# EVAL_51296_V2.net
KiCad netlist of a schematic drawn in EAGLE
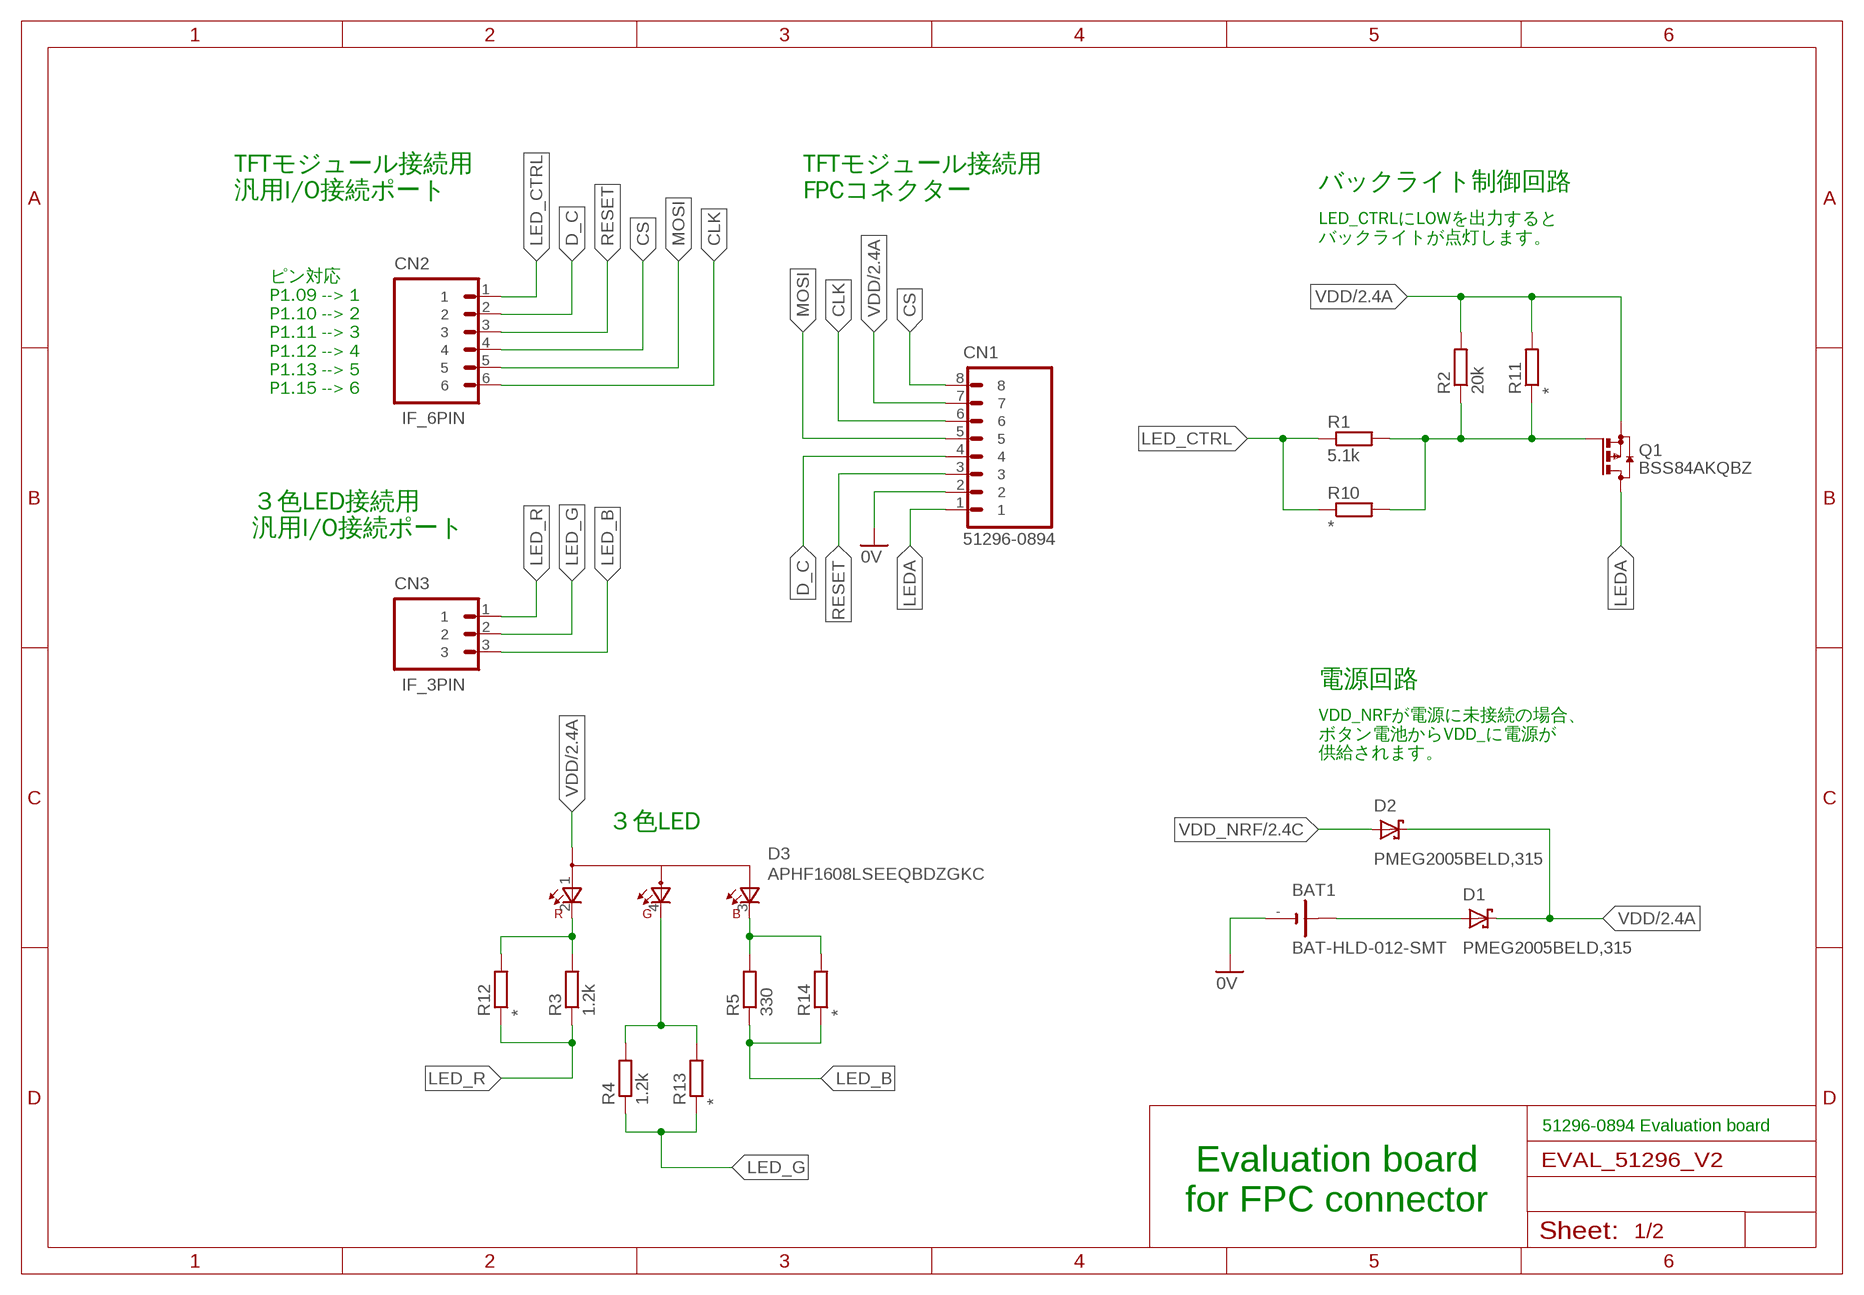
[diagram p0: schematic, sheet 1]
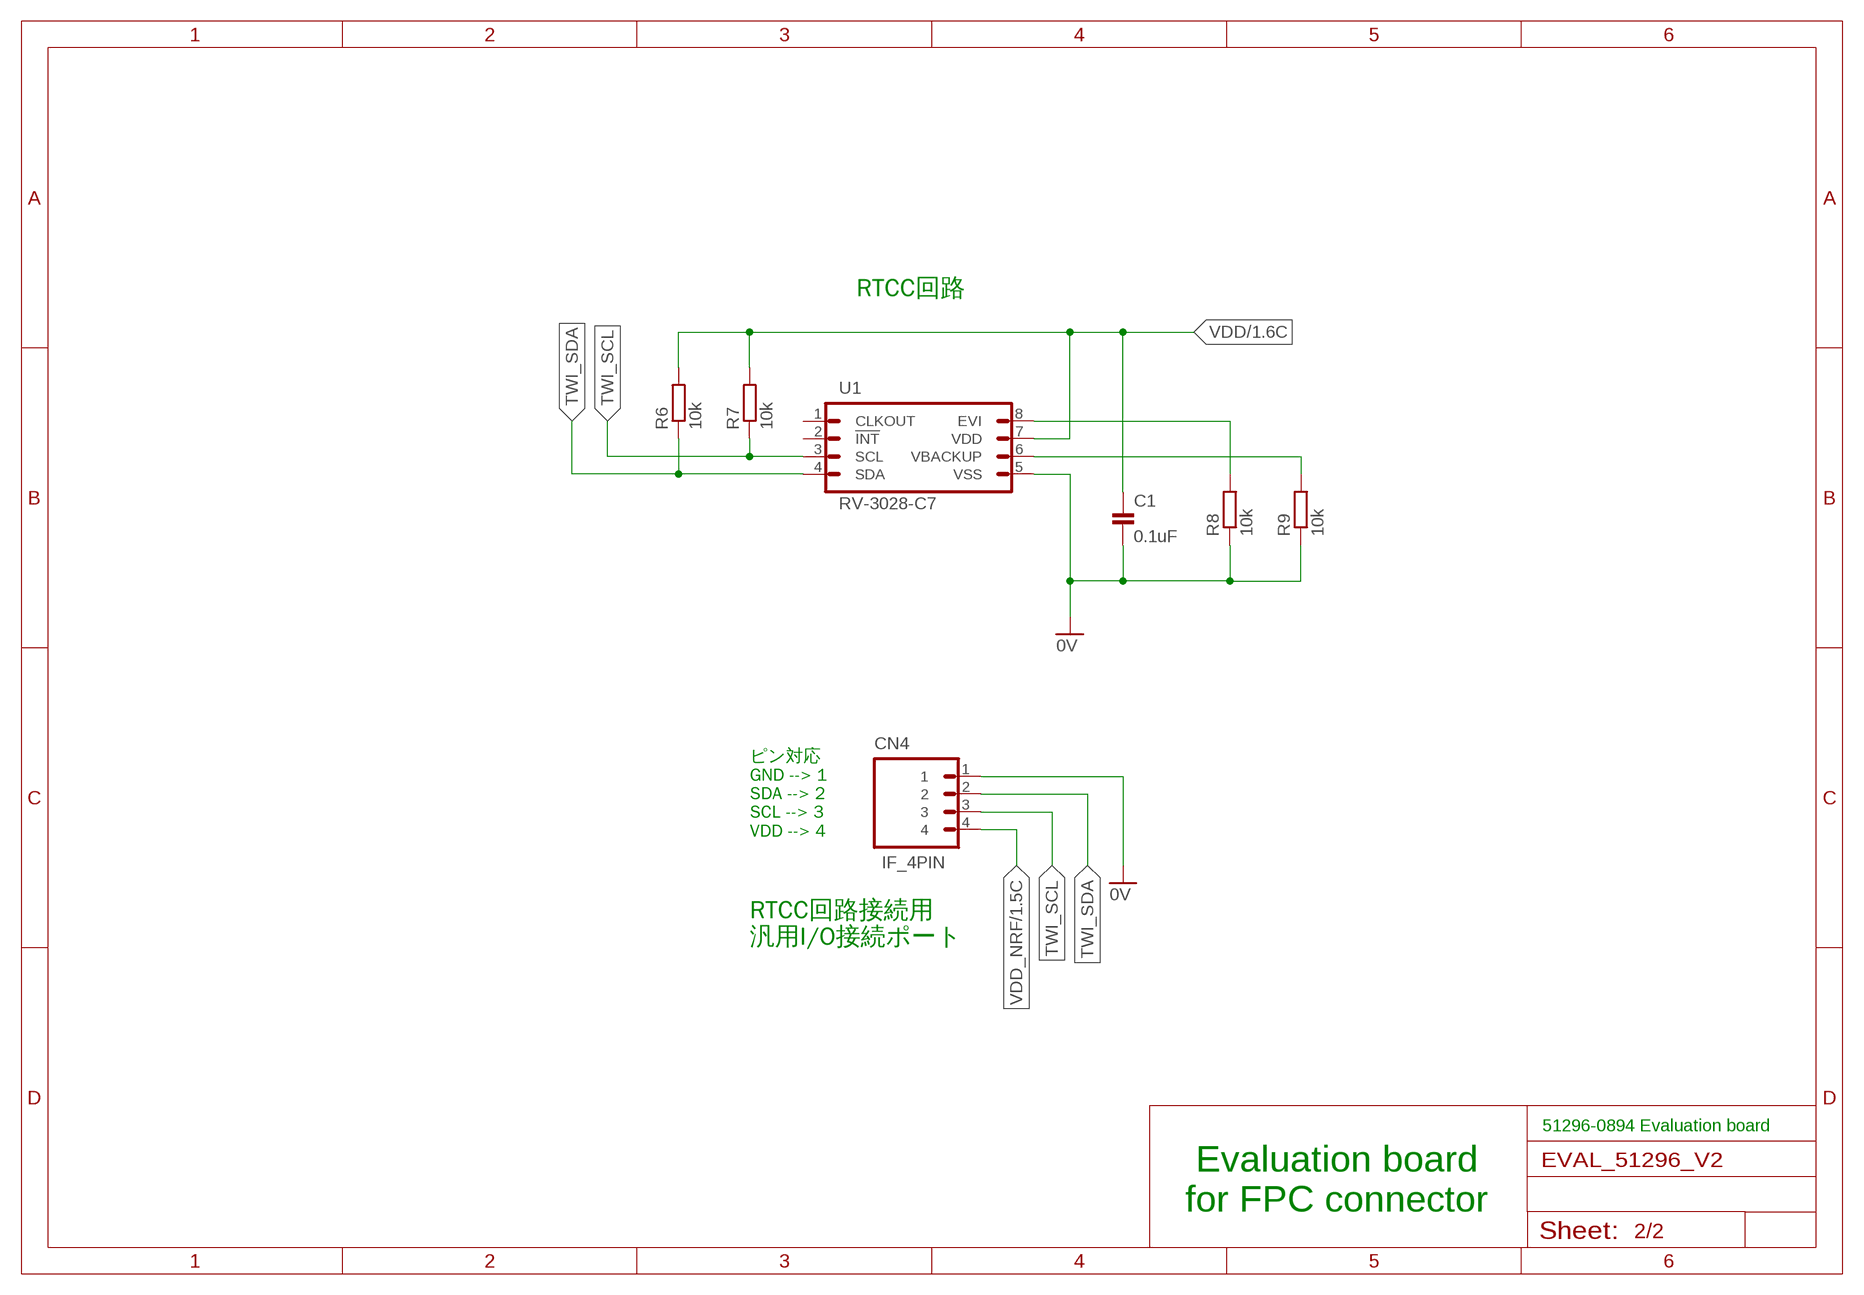
[diagram p1: schematic, sheet 2]

(export (version "E")
  (design (tool "Eeschema 10.0.6"))
  (components
    (comp (ref "BAT1")
      (value "BAT-HLD-012-SMT")
      (footprint "eagle-import:BAT-HLD-012-SMT")
      (libsource (lib "eagle-import") (part "BAT-HLD-012-SMT"))
    )
    (comp (ref "CN1")
      (value "51296-0894")
      (footprint "eagle-import:51296-0894")
      (libsource (lib "eagle-import") (part "51296-0894"))
    )
    (comp (ref "CN2")
      (value "IF_6PIN")
      (footprint "eagle-import:HEADER_6PIN")
      (libsource (lib "eagle-import") (part "IF_6PIN"))
    )
    (comp (ref "CN3")
      (value "IF_3PIN")
      (footprint "eagle-import:HEADER_3PIN")
      (libsource (lib "eagle-import") (part "IF_3PIN"))
    )
    (comp (ref "D1")
      (value "PMEG2005BELD,315")
      (footprint "eagle-import:DFN1006D-2")
      (libsource (lib "eagle-import") (part "PMEG2005BELD,315"))
    )
    (comp (ref "D2")
      (value "PMEG2005BELD,315")
      (footprint "eagle-import:DFN1006D-2")
      (libsource (lib "eagle-import") (part "PMEG2005BELD,315"))
    )
    (comp (ref "D3")
      (value "APHF1608LSEEQBDZGKC")
      (footprint "eagle-import:APHF1608LSEEQBDZGKC")
      (libsource (lib "eagle-import") (part "APHF1608LSEEQBDZGKC"))
    )
    (comp (ref "Q1")
      (value "BSS84AKQBZ")
      (footprint "eagle-import:BSS84AKQB")
      (libsource (lib "eagle-import") (part "BSS84AKQBZ"))
    )
    (comp (ref "R1")
      (value "5.1k")
      (footprint "eagle-import:R0402N")
      (libsource (lib "eagle-import") (part "RESISTOR_0402N"))
    )
    (comp (ref "R2")
      (value "20k")
      (footprint "eagle-import:R0402N")
      (libsource (lib "eagle-import") (part "RESISTOR_0402N"))
    )
    (comp (ref "R3")
      (value "1.2k")
      (footprint "eagle-import:R0402N")
      (libsource (lib "eagle-import") (part "RESISTOR_0402N"))
    )
    (comp (ref "R4")
      (value "1.2k")
      (footprint "eagle-import:R0402N")
      (libsource (lib "eagle-import") (part "RESISTOR_0402N"))
    )
    (comp (ref "R5")
      (value "330")
      (footprint "eagle-import:R0402N")
      (libsource (lib "eagle-import") (part "RESISTOR_0402N"))
    )
    (comp (ref "R10")
      (value "*")
      (footprint "eagle-import:RESISTOR_0204_200MIL")
      (libsource (lib "eagle-import") (part "RESISTOR_200MIL"))
    )
    (comp (ref "R11")
      (value "*")
      (footprint "eagle-import:RESISTOR_0204_200MIL")
      (libsource (lib "eagle-import") (part "RESISTOR_200MIL"))
    )
    (comp (ref "R12")
      (value "*")
      (footprint "eagle-import:RESISTOR_0204_200MIL")
      (libsource (lib "eagle-import") (part "RESISTOR_200MIL"))
    )
    (comp (ref "R13")
      (value "*")
      (footprint "eagle-import:RESISTOR_0204_200MIL")
      (libsource (lib "eagle-import") (part "RESISTOR_200MIL"))
    )
    (comp (ref "R14")
      (value "*")
      (footprint "eagle-import:RESISTOR_0204_200MIL")
      (libsource (lib "eagle-import") (part "RESISTOR_200MIL"))
    )
    (comp (ref "C1")
      (value "0.1uF")
      (footprint "eagle-import:C0402N")
      (libsource (lib "eagle-import") (part "CAP_0402N"))
    )
    (comp (ref "CN4")
      (value "IF_4PIN")
      (footprint "eagle-import:HEADER_4PIN")
      (libsource (lib "eagle-import") (part "IF_4PIN"))
    )
    (comp (ref "R6")
      (value "10k")
      (footprint "eagle-import:R0402N")
      (libsource (lib "eagle-import") (part "RESISTOR_0402N"))
    )
    (comp (ref "R7")
      (value "10k")
      (footprint "eagle-import:R0402N")
      (libsource (lib "eagle-import") (part "RESISTOR_0402N"))
    )
    (comp (ref "R8")
      (value "10k")
      (footprint "eagle-import:R0402N")
      (libsource (lib "eagle-import") (part "RESISTOR_0402N"))
    )
    (comp (ref "R9")
      (value "10k")
      (footprint "eagle-import:R0402N")
      (libsource (lib "eagle-import") (part "RESISTOR_0402N"))
    )
    (comp (ref "U1")
      (value "RV-3028-C7")
      (footprint "eagle-import:SON-8")
      (libsource (lib "eagle-import") (part "RV-3028-C7"))
    )
  )
  (nets
    (net (code "1") (name "0V") (class "Default")
      (node (ref "BAT1") (pin "-") (pinfunction "-_-") (pintype "passive"))
      (node (ref "C1") (pin "2") (pinfunction "2_2") (pintype "passive"))
      (node (ref "CN1") (pin "2") (pinfunction "2_2") (pintype "passive"))
      (node (ref "CN4") (pin "1") (pinfunction "1_1") (pintype "passive"))
      (node (ref "R8") (pin "1") (pinfunction "1_1") (pintype "passive"))
      (node (ref "R9") (pin "1") (pinfunction "1_1") (pintype "passive"))
      (node (ref "U1") (pin "5") (pinfunction "VSS_5") (pintype "passive"))
    )
    (net (code "2") (name "CLK") (class "Default")
      (node (ref "CN1") (pin "6") (pinfunction "6_6") (pintype "passive"))
      (node (ref "CN2") (pin "6") (pinfunction "6_6") (pintype "passive"))
    )
    (net (code "3") (name "CS") (class "Default")
      (node (ref "CN1") (pin "8") (pinfunction "8_8") (pintype "passive"))
      (node (ref "CN2") (pin "4") (pinfunction "4_4") (pintype "passive"))
    )
    (net (code "4") (name "D_C") (class "Default")
      (node (ref "CN1") (pin "4") (pinfunction "4_4") (pintype "passive"))
      (node (ref "CN2") (pin "2") (pinfunction "2_2") (pintype "passive"))
    )
    (net (code "5") (name "LEDA") (class "Default")
      (node (ref "CN1") (pin "1") (pinfunction "1_1") (pintype "passive"))
      (node (ref "Q1") (pin "3") (pinfunction "D_3") (pintype "passive"))
    )
    (net (code "6") (name "LED_B") (class "Default")
      (node (ref "CN3") (pin "3") (pinfunction "3_3") (pintype "passive"))
      (node (ref "R14") (pin "1") (pinfunction "1_1") (pintype "passive"))
      (node (ref "R5") (pin "1") (pinfunction "1_1") (pintype "passive"))
    )
    (net (code "7") (name "LED_CTRL") (class "Default")
      (node (ref "CN2") (pin "1") (pinfunction "1_1") (pintype "passive"))
      (node (ref "R1") (pin "1") (pinfunction "1_1") (pintype "passive"))
      (node (ref "R10") (pin "1") (pinfunction "1_1") (pintype "passive"))
    )
    (net (code "8") (name "LED_G") (class "Default")
      (node (ref "CN3") (pin "2") (pinfunction "2_2") (pintype "passive"))
      (node (ref "R13") (pin "1") (pinfunction "1_1") (pintype "passive"))
      (node (ref "R4") (pin "1") (pinfunction "1_1") (pintype "passive"))
    )
    (net (code "9") (name "LED_R") (class "Default")
      (node (ref "CN3") (pin "1") (pinfunction "1_1") (pintype "passive"))
      (node (ref "R12") (pin "1") (pinfunction "1_1") (pintype "passive"))
      (node (ref "R3") (pin "1") (pinfunction "1_1") (pintype "passive"))
    )
    (net (code "10") (name "MOSI") (class "Default")
      (node (ref "CN1") (pin "5") (pinfunction "5_5") (pintype "passive"))
      (node (ref "CN2") (pin "5") (pinfunction "5_5") (pintype "passive"))
    )
    (net (code "11") (name "Net-(BAT1-+)") (class "Default")
      (node (ref "BAT1") (pin "+@2") (pinfunction "+_+@2") (pintype "passive"))
      (node (ref "D1") (pin "2") (pinfunction "A_2") (pintype "passive"))
    )
    (net (code "12") (name "Net-(D3-CBLUE)") (class "Default")
      (node (ref "D3") (pin "3") (pinfunction "CBLUE_3") (pintype "passive"))
      (node (ref "R14") (pin "2") (pinfunction "2_2") (pintype "passive"))
      (node (ref "R5") (pin "2") (pinfunction "2_2") (pintype "passive"))
    )
    (net (code "13") (name "Net-(D3-CGREEN)") (class "Default")
      (node (ref "D3") (pin "4") (pinfunction "CGREEN_4") (pintype "passive"))
      (node (ref "R13") (pin "2") (pinfunction "2_2") (pintype "passive"))
      (node (ref "R4") (pin "2") (pinfunction "2_2") (pintype "passive"))
    )
    (net (code "14") (name "Net-(D3-CRED)") (class "Default")
      (node (ref "D3") (pin "2") (pinfunction "CRED_2") (pintype "passive"))
      (node (ref "R12") (pin "2") (pinfunction "2_2") (pintype "passive"))
      (node (ref "R3") (pin "2") (pinfunction "2_2") (pintype "passive"))
    )
    (net (code "15") (name "Net-(Q1-G)") (class "Default")
      (node (ref "Q1") (pin "1") (pinfunction "G_1") (pintype "passive"))
      (node (ref "R1") (pin "2") (pinfunction "2_2") (pintype "passive"))
      (node (ref "R10") (pin "2") (pinfunction "2_2") (pintype "passive"))
      (node (ref "R11") (pin "1") (pinfunction "1_1") (pintype "passive"))
      (node (ref "R2") (pin "1") (pinfunction "1_1") (pintype "passive"))
    )
    (net (code "16") (name "Net-(U1-EVI)") (class "Default")
      (node (ref "R8") (pin "2") (pinfunction "2_2") (pintype "passive"))
      (node (ref "U1") (pin "8") (pinfunction "EVI_8") (pintype "bidirectional"))
    )
    (net (code "17") (name "Net-(U1-VBACKUP)") (class "Default")
      (node (ref "R9") (pin "2") (pinfunction "2_2") (pintype "passive"))
      (node (ref "U1") (pin "6") (pinfunction "VBACKUP_6") (pintype "passive"))
    )
    (net (code "18") (name "RESET") (class "Default")
      (node (ref "CN1") (pin "3") (pinfunction "3_3") (pintype "passive"))
      (node (ref "CN2") (pin "3") (pinfunction "3_3") (pintype "passive"))
    )
    (net (code "19") (name "TWI_SCL") (class "Default")
      (node (ref "CN4") (pin "3") (pinfunction "3_3") (pintype "passive"))
      (node (ref "R7") (pin "1") (pinfunction "1_1") (pintype "passive"))
      (node (ref "U1") (pin "3") (pinfunction "SCL_3") (pintype "bidirectional"))
    )
    (net (code "20") (name "TWI_SDA") (class "Default")
      (node (ref "CN4") (pin "2") (pinfunction "2_2") (pintype "passive"))
      (node (ref "R6") (pin "1") (pinfunction "1_1") (pintype "passive"))
      (node (ref "U1") (pin "4") (pinfunction "SDA_4") (pintype "bidirectional"))
    )
    (net (code "21") (name "VDD") (class "Default")
      (node (ref "C1") (pin "1") (pinfunction "1_1") (pintype "passive"))
      (node (ref "CN1") (pin "7") (pinfunction "7_7") (pintype "passive"))
      (node (ref "D1") (pin "1") (pinfunction "C_1") (pintype "passive"))
      (node (ref "D2") (pin "1") (pinfunction "C_1") (pintype "passive"))
      (node (ref "D3") (pin "1") (pinfunction "A_1") (pintype "passive"))
      (node (ref "Q1") (pin "2") (pinfunction "S_2") (pintype "passive"))
      (node (ref "R11") (pin "2") (pinfunction "2_2") (pintype "passive"))
      (node (ref "R2") (pin "2") (pinfunction "2_2") (pintype "passive"))
      (node (ref "R6") (pin "2") (pinfunction "2_2") (pintype "passive"))
      (node (ref "R7") (pin "2") (pinfunction "2_2") (pintype "passive"))
      (node (ref "U1") (pin "7") (pinfunction "VDD_7") (pintype "passive"))
    )
    (net (code "22") (name "VDD_NRF") (class "Default")
      (node (ref "CN4") (pin "4") (pinfunction "4_4") (pintype "passive"))
      (node (ref "D2") (pin "2") (pinfunction "A_2") (pintype "passive"))
    )
    (net (code "23") (name "unconnected-(U1-CLKOUT-Pad1)") (class "Default")
      (node (ref "U1") (pin "1") (pinfunction "CLKOUT_1") (pintype "bidirectional"))
    )
    (net (code "24") (name "unconnected-(U1-~{INT}-Pad2)") (class "Default")
      (node (ref "U1") (pin "2") (pinfunction "~{INT}_2") (pintype "bidirectional"))
    )
  )
)
